# EPS_Headers.net
KiCad netlist of a schematic drawn in Altium Designer
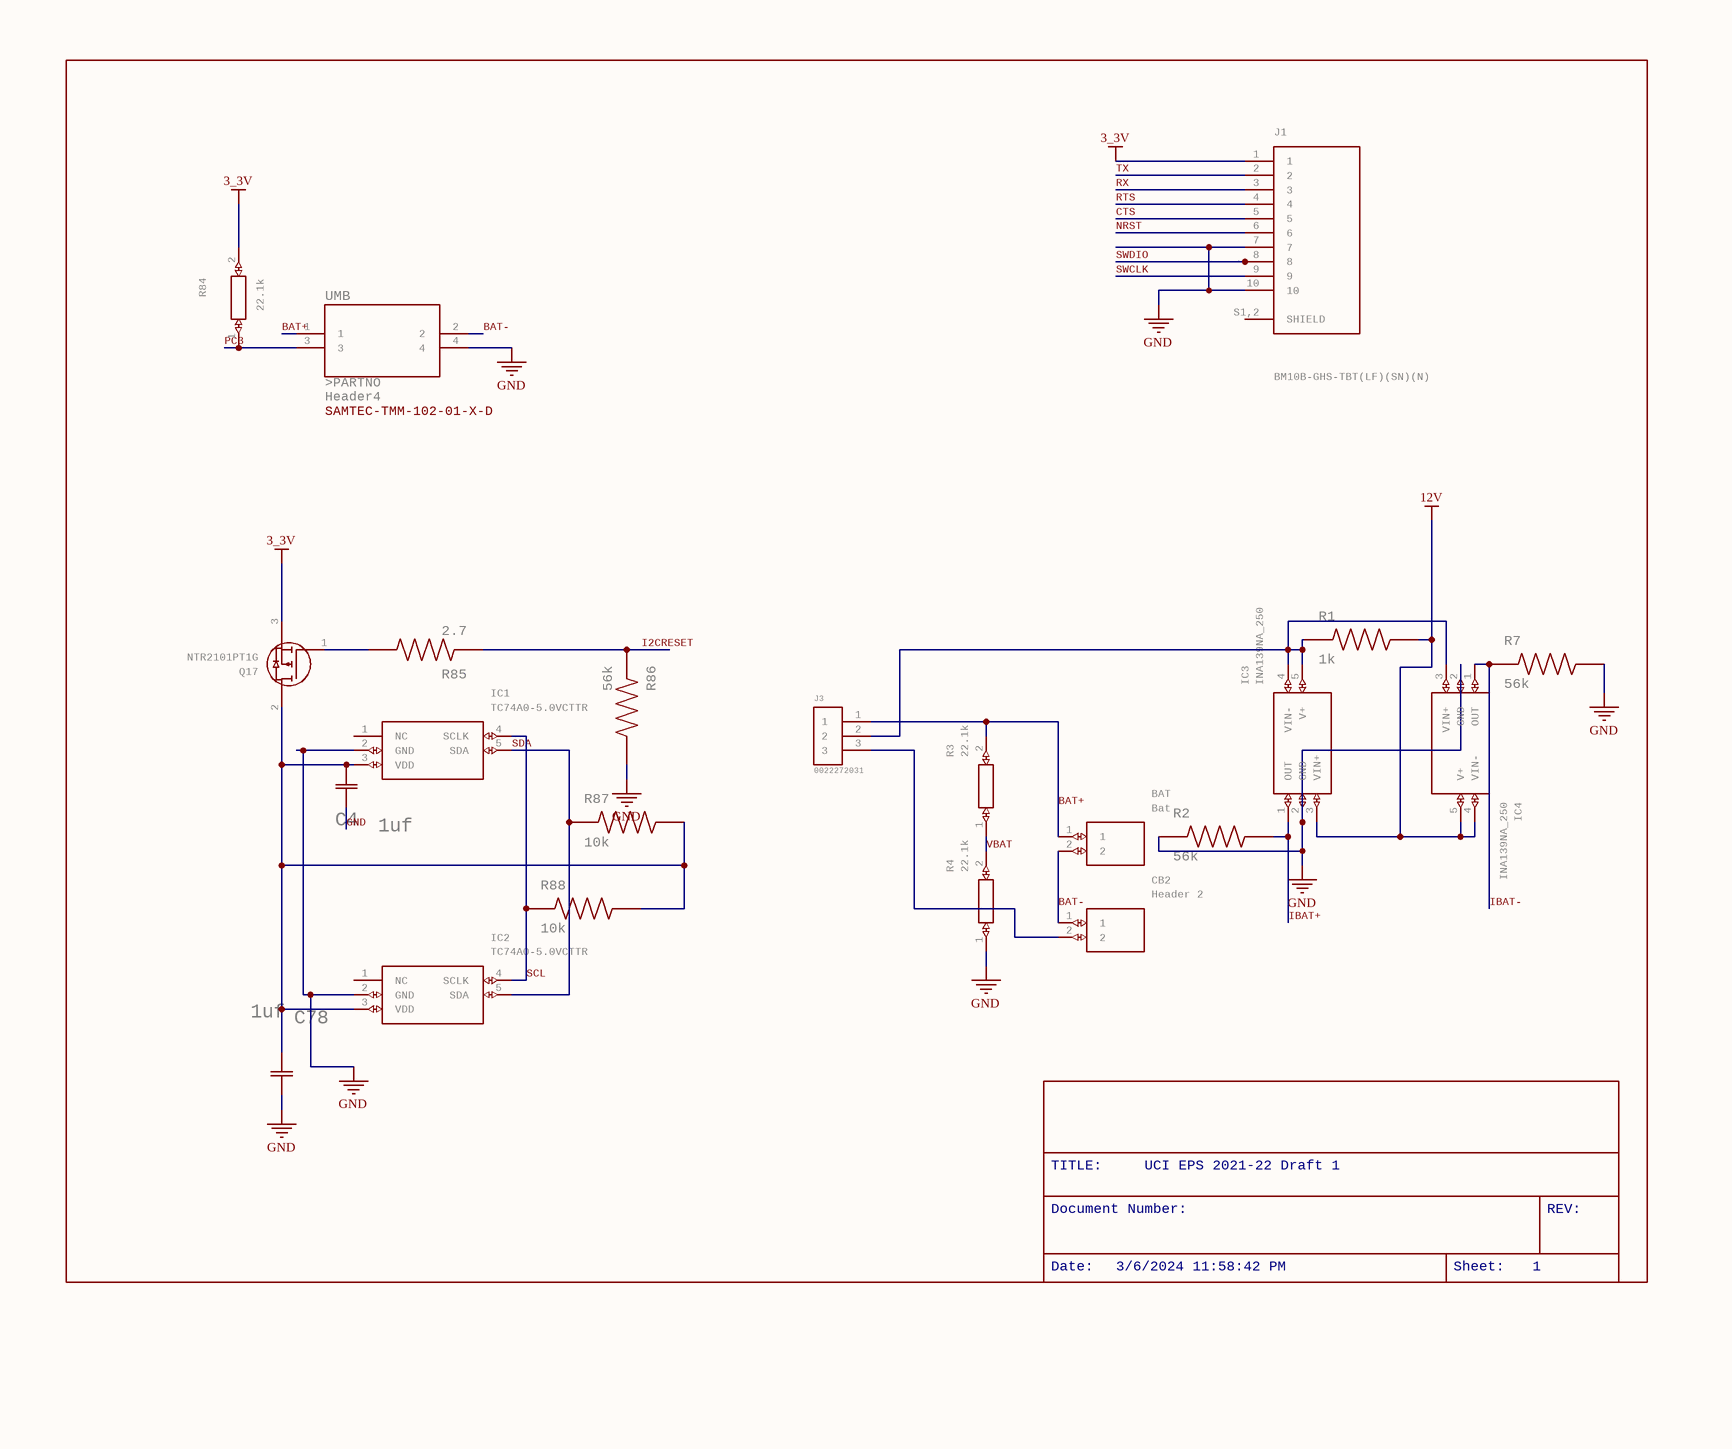
[diagram p0: EPS_Headers.SchDoc]

(export (version "E")
  (design (tool "Eeschema 10.0.6"))
  (components
    (comp (ref "BAT")
      (value "Bat")
      (footprint "SHDR2W64P0X254_1X2_508X580X117")
      (description "Conn Wire to Board HDR 2 POS 2.54mm Solder ST Thru-Hole KK Bag   Source:  Datasheet")
      (fields (field (name "ARROW_PART_NUMBER") "0022272021"))
      (libsource (lib "header 2") (part "0022272021"))
    )
    (comp (ref "C4")
      (value "1uf")
      (footprint "YAG_CC0603_YAG-L")
      (fields (field (name "MANUFACTURER_PART_NUMBER") "CC0603KRX7R7BB105"))
      (libsource (lib "Cap 1uf") (part "CC0603KRX7R7BB105YAG_CC0603_YAG-L"))
    )
    (comp (ref "C78")
      (value "1uf")
      (footprint "YAG_CC0603_YAG")
      (fields (field (name "MANUFACTURER_PART_NUMBER") "CC0603KRX7R7BB105"))
      (libsource (lib "Cap 1uf") (part "CC0603KRX7R7BB105"))
    )
    (comp (ref "CB2")
      (value "Header 2")
      (footprint "SHDR2W64P0X254_1X2_508X580X117")
      (description "Conn Wire to Board HDR 2 POS 2.54mm Solder ST Thru-Hole KK Bag   Source:  Datasheet")
      (fields (field (name "ARROW_PART_NUMBER") "0022272021"))
      (libsource (lib "header 2") (part "0022272021"))
    )
    (comp (ref "IC1")
      (value "TC74A0-5.0VCTTR")
      (footprint "SOT95P280X145-5N")
      (description "Serial Digital Thermal Sensor   Source:  Datasheet")
      (fields (field (name "MOUSER_PART_NUMBER") "579-TC74A0-5.0VCTTR"))
      (libsource (lib "TC74A0-5.0VCTTR") (part "TC74A0-5.0VCTTR"))
    )
    (comp (ref "IC2")
      (value "TC74A0-5.0VCTTR")
      (footprint "SOT95P280X145-5N")
      (description "Serial Digital Thermal Sensor   Source:  Datasheet")
      (fields (field (name "MOUSER_PART_NUMBER") "579-TC74A0-5.0VCTTR"))
      (libsource (lib "TC74A0-5.0VCTTR") (part "TC74A0-5.0VCTTR"))
    )
    (comp (ref "IC3")
      (value "INA139NA_250")
      (footprint "SOT95P280X145-5N")
      (description "36V, High-Side, High-Speed, Current Output Current Sense Amplifier   Source:  Datasheet")
      (fields
        (field (name "ARROW_PART_NUMBER") "INA139NA/250")
        (field (name "MOUSER_PART_NUMBER") "595-INA139NA/250")
      )
      (libsource (lib "INA139NA_250") (part "INA139NA_250"))
    )
    (comp (ref "IC4")
      (value "INA139NA_250")
      (footprint "SOT95P280X145-5N")
      (description "36V, High-Side, High-Speed, Current Output Current Sense Amplifier   Source:  Datasheet")
      (fields
        (field (name "ARROW_PART_NUMBER") "INA139NA/250")
        (field (name "MOUSER_PART_NUMBER") "595-INA139NA/250")
      )
      (libsource (lib "INA139NA_250") (part "INA139NA_250"))
    )
    (comp (ref "J1")
      (value "BM10B-GHS-TBT(LF)(SN)(N)")
      (footprint "JST_BM10B-GHS-TBT(LF)(SN)(N)")
      (description "Connector Header Surface Mount 10 position 0.049\" (1.25mm) Check prices")
      (fields (field (name "MF") "JST Sales"))
      (libsource (lib "BM10B-GHS-TBT_LF__SN__N_") (part "BM10B-GHS-TBT(LF)(SN)(N)"))
    )
    (comp (ref "J3")
      (value "0022272031")
      (footprint "MOLEX_0022272031")
      (description "CONN HEADER 3POS .100 VERT TIN Check prices")
      (fields (field (name "MF") "Molex"))
      (libsource (lib "header 3") (part "0022272031"))
    )
    (comp (ref "Q17")
      (value "NTR2101PT1G")
      (footprint "SOT96P237X111-3N")
      (description "Small Signal MOSFET   Source:  Datasheet")
      (fields (field (name "MOUSER_PART_NUMBER") "863-NTR2101PT1G"))
      (libsource (lib "MOSFET-P") (part "NTR2101PT1G"))
    )
    (comp (ref "R1")
      (value "1k")
      (footprint "RESC1608X55N")
      (description "Res Thick Film 0603 1K Ohm 5% 0.2W(1/5W) Â±50ppm/C Pad SMD Automotive T/R")
      (fields (field (name "DIGI-KEY_PART_NUMBER") "P20283CT-ND") (field (name "MF") "Panasonic"))
      (libsource (lib "Res1 1k") (part "ERJ-PB3D1001V"))
    )
    (comp (ref "R2")
      (value "56k")
      (footprint "RESC1608X55N")
      (description "RES SMD 56K OHM 0.5% 1/5W 0603")
      (fields (field (name "DIGI-KEY_PART_NUMBER") "DIGI-KEY_PART_NUMBER") (field (name "MF") "Panasonic"))
      (libsource (lib "Res1 56k") (part "ERJ-PB3D5602V"))
    )
    (comp (ref "R3")
      (value "22.1k")
      (footprint "RESC1608X55N")
      (description "hj   Source:  Datasheet")
      (fields
        (field (name "ARROW_PART_NUMBER") "ARROW_PART_NUMBER")
        (field (name "MANUFACTURER_PART_NUMBER") "ERJPB3D2212V")
      )
      (libsource (lib "Res1-22.1k") (part "ERJPB3D2212V"))
    )
    (comp (ref "R4")
      (value "22.1k")
      (footprint "RESC1608X55N")
      (description "hj   Source:  Datasheet")
      (fields
        (field (name "ARROW_PART_NUMBER") "ARROW_PART_NUMBER")
        (field (name "MANUFACTURER_PART_NUMBER") "ERJPB3D2212V")
      )
      (libsource (lib "Res1-22.1k") (part "ERJPB3D2212V"))
    )
    (comp (ref "R7")
      (value "56k")
      (footprint "RESC1608X55N")
      (description "RES SMD 56K OHM 0.5% 1/5W 0603")
      (fields (field (name "DIGI-KEY_PART_NUMBER") "DIGI-KEY_PART_NUMBER") (field (name "MF") "Panasonic"))
      (libsource (lib "Res1 56k") (part "ERJ-PB3D5602V"))
    )
    (comp (ref "R84")
      (value "22.1k")
      (footprint "RESC1608X55N")
      (description "hj   Source:  Datasheet")
      (fields
        (field (name "ARROW_PART_NUMBER") "ARROW_PART_NUMBER")
        (field (name "MANUFACTURER_PART_NUMBER") "ERJPB3D2212V")
      )
      (libsource (lib "Res1-22.1k") (part "ERJPB3D2212V"))
    )
    (comp (ref "R85")
      (value "2.7")
      (footprint "RESC1608X55N")
      (fields
        (field (name "DIGI-KEY_PART_NUMBER") "DIGI-KEY_PART_NUMBER")
        (field (name "MF") "Susumu")
        (field (name "MP") "RL0816S-2R7-F")
      )
      (libsource (lib "Res1-2.7") (part "RL0816S-2R7-F"))
    )
    (comp (ref "R86")
      (value "56k")
      (footprint "RESC1608X55N")
      (description "RES SMD 56K OHM 0.5% 1/5W 0603")
      (fields (field (name "DIGI-KEY_PART_NUMBER") "DIGI-KEY_PART_NUMBER") (field (name "MF") "Panasonic"))
      (libsource (lib "Res1 56k") (part "ERJ-PB3D5602V"))
    )
    (comp (ref "R87")
      (value "10k")
      (footprint "RESC1608X55N")
      (description "Res Thick Film 0603 10K Ohm 5% 0.2W(1/5W) Â±50ppm/C Pad SMD Automotive T/R")
      (fields
        (field (name "DIGI-KEY_PART_NUMBER") "DIGI-KEY_PART_NUMBER")
        (field (name "MF") "Panasonic Electronic")
      )
      (libsource (lib "Res1 10k") (part "ERJ-PB3D1002V"))
    )
    (comp (ref "R88")
      (value "10k")
      (footprint "RESC1608X55N")
      (description "Res Thick Film 0603 10K Ohm 5% 0.2W(1/5W) Â±50ppm/C Pad SMD Automotive T/R")
      (fields
        (field (name "DIGI-KEY_PART_NUMBER") "DIGI-KEY_PART_NUMBER")
        (field (name "MF") "Panasonic Electronic")
      )
      (libsource (lib "Res1 10k") (part "ERJ-PB3D1002V"))
    )
    (comp (ref "UMB")
      (value "Header4")
      (footprint "SAMTEC-TMM-102-01-X-D")
      (description "Check prices")
      (fields
        (field (name "PARTNO") ">PARTNO")
        (field (name "SAMTEC-TMM-102-01-X-D") "SAMTEC-TMM-102-01-X-D")
        (field (name "MF") "Samtec Inc.")
        (field (name "MP") "TMM-102-01-T-D")
        (field (name "LIBRARYNAME") "4 pin header replace")
      )
      (libsource (lib "4 pin header replace") (part "SAMTEC-TMM-102-01-X-DJ"))
    )
  )
  (nets
    (net (code "1") (name "/BAT+") (class "Default")
      (node (ref "BAT") (pin "1") (pinfunction "1_1") (pintype "bidirectional"))
      (node (ref "J3") (pin "1") (pinfunction "1_1") (pintype "passive"))
      (node (ref "R3") (pin "2") (pinfunction "2_2") (pintype "bidirectional"))
      (node (ref "UMB") (pin "1") (pinfunction "1_1") (pintype "passive"))
    )
    (net (code "2") (name "/BAT-") (class "Default")
      (node (ref "BAT") (pin "2") (pinfunction "2_2") (pintype "bidirectional"))
      (node (ref "CB2") (pin "1") (pinfunction "1_1") (pintype "bidirectional"))
      (node (ref "UMB") (pin "2") (pinfunction "2_2") (pintype "passive"))
    )
    (net (code "3") (name "/CTS") (class "Default")
      (node (ref "J1") (pin "5") (pinfunction "5_5") (pintype "passive"))
    )
    (net (code "4") (name "/I2CRESET") (class "Default")
      (node (ref "R85") (pin "1") (pinfunction "1_1") (pintype "passive"))
      (node (ref "R86") (pin "1") (pinfunction "1_1") (pintype "passive"))
    )
    (net (code "5") (name "/IBAT+") (class "Default")
      (node (ref "IC3") (pin "1") (pinfunction "OUT_1") (pintype "bidirectional"))
      (node (ref "R2") (pin "2") (pinfunction "2_2") (pintype "passive"))
    )
    (net (code "6") (name "/IBAT-") (class "Default")
      (node (ref "IC4") (pin "1") (pinfunction "OUT_1") (pintype "bidirectional"))
      (node (ref "R7") (pin "1") (pinfunction "1_1") (pintype "passive"))
    )
    (net (code "7") (name "/NRST") (class "Default")
      (node (ref "J1") (pin "6") (pinfunction "6_6") (pintype "passive"))
    )
    (net (code "8") (name "/PC3") (class "Default")
      (node (ref "R84") (pin "1") (pinfunction "1_1") (pintype "bidirectional"))
      (node (ref "UMB") (pin "3") (pinfunction "3_3") (pintype "passive"))
    )
    (net (code "9") (name "/RTS") (class "Default")
      (node (ref "J1") (pin "4") (pinfunction "4_4") (pintype "passive"))
    )
    (net (code "10") (name "/RX") (class "Default")
      (node (ref "J1") (pin "3") (pinfunction "3_3") (pintype "passive"))
    )
    (net (code "11") (name "/SCL") (class "Default")
      (node (ref "IC1") (pin "4") (pinfunction "SCLK_4") (pintype "bidirectional"))
      (node (ref "IC2") (pin "4") (pinfunction "SCLK_4") (pintype "bidirectional"))
      (node (ref "R88") (pin "1") (pinfunction "1_1") (pintype "passive"))
    )
    (net (code "12") (name "/SDA") (class "Default")
      (node (ref "IC1") (pin "5") (pinfunction "SDA_5") (pintype "bidirectional"))
      (node (ref "IC2") (pin "5") (pinfunction "SDA_5") (pintype "bidirectional"))
      (node (ref "R87") (pin "1") (pinfunction "1_1") (pintype "passive"))
    )
    (net (code "13") (name "/SWCLK") (class "Default")
      (node (ref "J1") (pin "9") (pinfunction "9_9") (pintype "passive"))
    )
    (net (code "14") (name "/SWDIO") (class "Default")
      (node (ref "J1") (pin "8") (pinfunction "8_8") (pintype "passive"))
    )
    (net (code "15") (name "/TX") (class "Default")
      (node (ref "J1") (pin "2") (pinfunction "2_2") (pintype "passive"))
    )
    (net (code "16") (name "/VBAT") (class "Default")
      (node (ref "R3") (pin "1") (pinfunction "1_1") (pintype "bidirectional"))
      (node (ref "R4") (pin "2") (pinfunction "2_2") (pintype "bidirectional"))
    )
    (net (code "17") (name "3_3V") (class "Default")
      (node (ref "J1") (pin "1") (pinfunction "1_1") (pintype "passive"))
      (node (ref "Q17") (pin "3") (pinfunction "D_3") (pintype "bidirectional"))
      (node (ref "R84") (pin "2") (pinfunction "2_2") (pintype "bidirectional"))
    )
    (net (code "18") (name "12V") (class "Default")
      (node (ref "IC3") (pin "3") (pinfunction "VIN+_3") (pintype "bidirectional"))
      (node (ref "IC4") (pin "4") (pinfunction "VIN-_4") (pintype "bidirectional"))
      (node (ref "IC4") (pin "5") (pinfunction "V+_5") (pintype "bidirectional"))
      (node (ref "R1") (pin "2") (pinfunction "2_2") (pintype "passive"))
    )
    (net (code "19") (name "GND") (class "Default")
      (node (ref "C4") (pin "1") (pinfunction "1_1") (pintype "passive"))
      (node (ref "C78") (pin "2") (pinfunction "2_2") (pintype "passive"))
      (node (ref "IC1") (pin "2") (pinfunction "GND_2") (pintype "bidirectional"))
      (node (ref "IC2") (pin "2") (pinfunction "GND_2") (pintype "bidirectional"))
      (node (ref "IC3") (pin "2") (pinfunction "GND_2") (pintype "bidirectional"))
      (node (ref "IC4") (pin "2") (pinfunction "GND_2") (pintype "bidirectional"))
      (node (ref "J1") (pin "10") (pinfunction "10_10") (pintype "passive"))
      (node (ref "J1") (pin "7") (pinfunction "7_7") (pintype "passive"))
      (node (ref "R2") (pin "1") (pinfunction "1_1") (pintype "passive"))
      (node (ref "R4") (pin "1") (pinfunction "1_1") (pintype "bidirectional"))
      (node (ref "R7") (pin "2") (pinfunction "2_2") (pintype "passive"))
      (node (ref "R86") (pin "2") (pinfunction "2_2") (pintype "passive"))
      (node (ref "UMB") (pin "4") (pinfunction "4_4") (pintype "passive"))
    )
    (net (code "20") (name "Net-(CB2-Pad2)") (class "Default")
      (node (ref "CB2") (pin "2") (pinfunction "2_2") (pintype "bidirectional"))
      (node (ref "J3") (pin "3") (pinfunction "3_3") (pintype "passive"))
    )
    (net (code "21") (name "Net-(IC1-VDD)") (class "Default")
      (node (ref "C4") (pin "2") (pinfunction "2_2") (pintype "passive"))
      (node (ref "C78") (pin "1") (pinfunction "1_1") (pintype "passive"))
      (node (ref "IC1") (pin "3") (pinfunction "VDD_3") (pintype "bidirectional"))
      (node (ref "IC2") (pin "3") (pinfunction "VDD_3") (pintype "bidirectional"))
      (node (ref "Q17") (pin "2") (pinfunction "S_2") (pintype "bidirectional"))
      (node (ref "R87") (pin "2") (pinfunction "2_2") (pintype "passive"))
      (node (ref "R88") (pin "2") (pinfunction "2_2") (pintype "passive"))
    )
    (net (code "22") (name "Net-(IC3-V+)") (class "Default")
      (node (ref "IC3") (pin "4") (pinfunction "VIN-_4") (pintype "bidirectional"))
      (node (ref "IC3") (pin "5") (pinfunction "V+_5") (pintype "bidirectional"))
      (node (ref "IC4") (pin "3") (pinfunction "VIN+_3") (pintype "bidirectional"))
      (node (ref "J3") (pin "2") (pinfunction "2_2") (pintype "passive"))
      (node (ref "R1") (pin "1") (pinfunction "1_1") (pintype "passive"))
    )
    (net (code "23") (name "Net-(Q17-G)") (class "Default")
      (node (ref "Q17") (pin "1") (pinfunction "G_1") (pintype "bidirectional"))
      (node (ref "R85") (pin "2") (pinfunction "2_2") (pintype "passive"))
    )
    (net (code "24") (name "unconnected-(IC1-NC-Pad1)") (class "Default")
      (node (ref "IC1") (pin "1") (pinfunction "NC_1") (pintype "passive"))
    )
    (net (code "25") (name "unconnected-(IC2-NC-Pad1)") (class "Default")
      (node (ref "IC2") (pin "1") (pinfunction "NC_1") (pintype "passive"))
    )
    (net (code "26") (name "unconnected-(J1-SHIELD-PadS1)") (class "Default")
      (node (ref "J1") (pin "S1") (pinfunction "SHIELD_S1") (pintype "passive"))
      (node (ref "J1") (pin "2") (pinfunction "SHIELD_2") (pintype "passive"))
    )
  )
)
